# ControllerPrint.net
KiCad netlist of a schematic drawn in Altium Designer
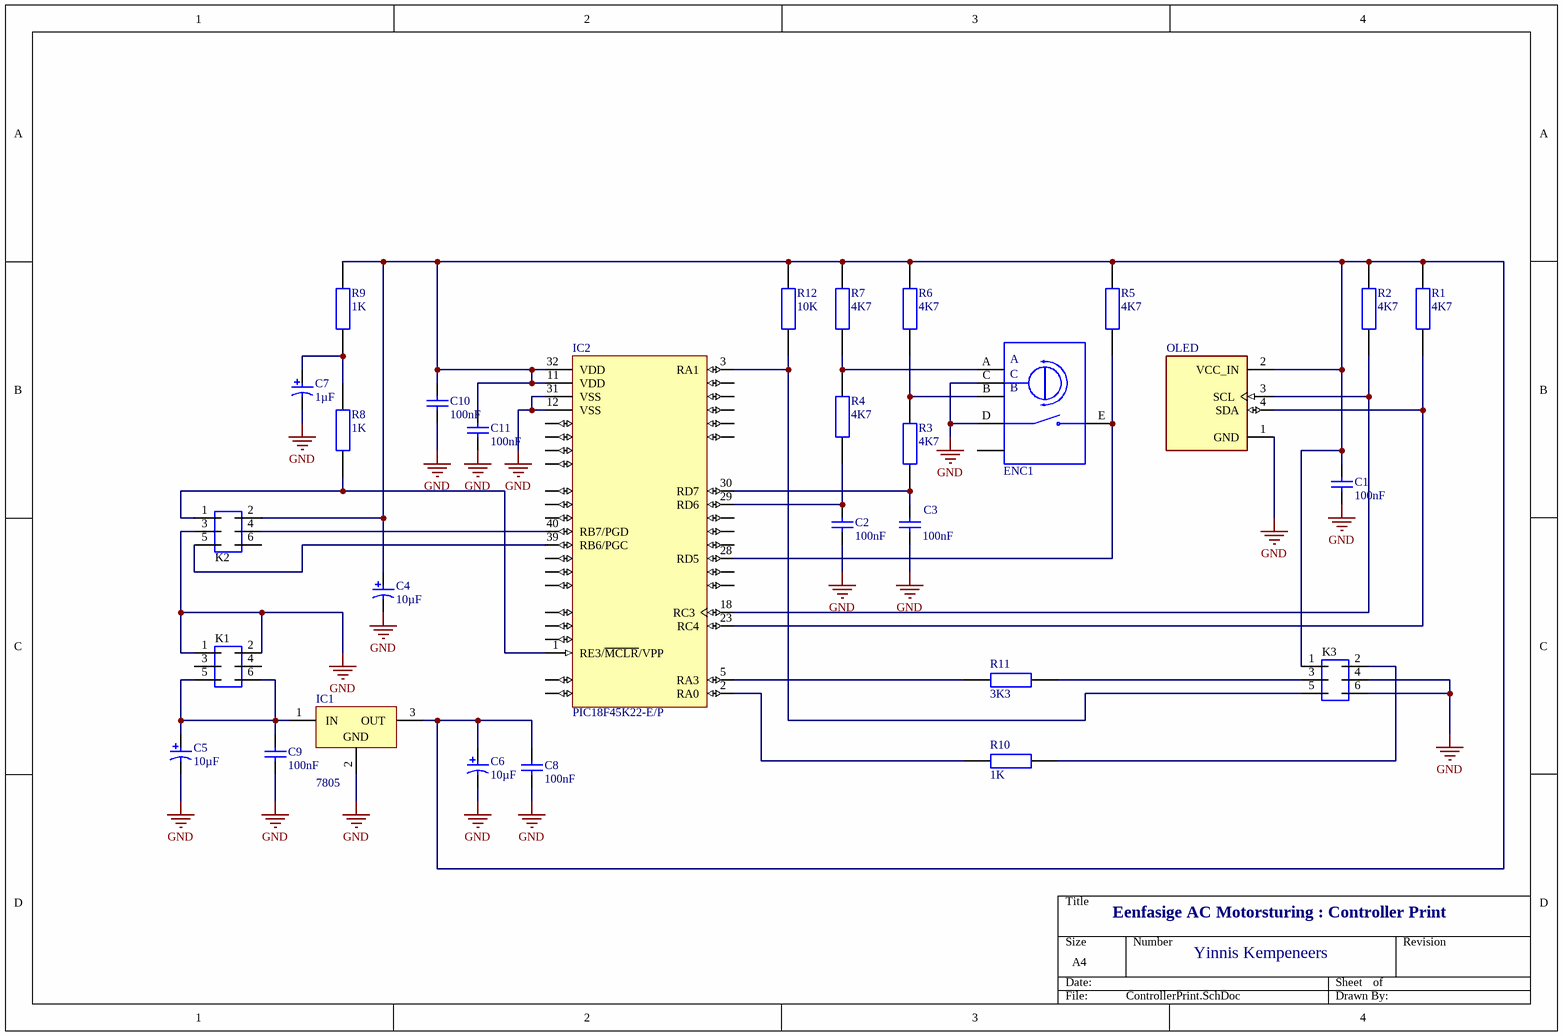
[diagram p0: ControllerPrint.SchDoc]

(export (version "E")
  (design (tool "Eeschema 10.0.6"))
  (components
    (comp (ref "C1")
      (value "100nF")
      (footprint "Capacitor 100nF")
      (libsource (lib "Schlib_Motorsturing") (part "Capacitor 100nF"))
    )
    (comp (ref "C2")
      (value "100nF")
      (footprint "Capacitor 100nF")
      (libsource (lib "Schlib_Motorsturing") (part "Capacitor 100nF"))
    )
    (comp (ref "C3")
      (value "100nF")
      (footprint "Capacitor 100nF")
      (libsource (lib "Schlib_Motorsturing") (part "Capacitor 100nF"))
    )
    (comp (ref "C4")
      (value "10µF")
      (footprint "Capacitor 10µF")
      (description "Aluminum Electrolytic Capacitor, 10 uF, +/- 20%, 50 V, -40 to 85 degC, 2-Pin THD, RoHS, Bulk")
      (fields (field (name "MANUFACTURER") "Panasonic") (field (name "TOLERANCE") "20%"))
      (libsource (lib "Schlib_Motorsturing") (part "Capacitor 10µF"))
    )
    (comp (ref "C5")
      (value "10µF")
      (footprint "Capacitor 10µF")
      (description "Aluminum Electrolytic Capacitor, 10 uF, +/- 20%, 50 V, -40 to 85 degC, 2-Pin THD, RoHS, Bulk")
      (fields (field (name "MANUFACTURER") "Panasonic") (field (name "TOLERANCE") "20%"))
      (libsource (lib "Schlib_Motorsturing") (part "Capacitor 10µF"))
    )
    (comp (ref "C6")
      (value "10µF")
      (footprint "Capacitor 10µF")
      (description "Aluminum Electrolytic Capacitor, 10 uF, +/- 20%, 50 V, -40 to 85 degC, 2-Pin THD, RoHS, Bulk")
      (fields (field (name "MANUFACTURER") "Panasonic") (field (name "TOLERANCE") "20%"))
      (libsource (lib "Schlib_Motorsturing") (part "Capacitor 10µF"))
    )
    (comp (ref "C7")
      (value "1µF")
      (footprint "Capacitor 10µF")
      (description "Aluminum 1µ Electrolytic Capacitor, 1 uF, +/- 20%, 50 V, -40 to 85 degC, 2-Pin THD, RoHS, Bulk")
      (fields (field (name "MANUFACTURER") "Panasonic") (field (name "TOLERANCE") "20%"))
      (libsource (lib "Schlib_Motorsturing") (part "Capacitor 10µF"))
    )
    (comp (ref "C8")
      (value "100nF")
      (footprint "Capacitor 100nF")
      (libsource (lib "Schlib_Motorsturing") (part "Capacitor 100nF"))
    )
    (comp (ref "C9")
      (value "100nF")
      (footprint "Capacitor 100nF")
      (libsource (lib "Schlib_Motorsturing") (part "Capacitor 100nF"))
    )
    (comp (ref "C10")
      (value "100nF")
      (footprint "Capacitor 100nF")
      (libsource (lib "Schlib_Motorsturing") (part "Capacitor 100nF"))
    )
    (comp (ref "C11")
      (value "100nF")
      (footprint "Capacitor 100nF")
      (libsource (lib "Schlib_Motorsturing") (part "Capacitor 100nF"))
    )
    (comp (ref "ENC1")
      (value "EC12E2424407")
      (footprint "ENC1_PCB")
      (description "Encoders 12mm 24 Res 24 Dtent 20mm op sectn w/ sw")
      (fields (field (name "MF") "ALPS"))
      (libsource (lib "Schlib1") (part "ENC1"))
    )
    (comp (ref "IC1")
      (value "7805")
      (footprint "MC7805CTG")
      (description "Positive Voltage Regulator, 1 A, 5 V, 0 to 125 degC, 3-Pin TO-220, RoHS, Tube")
      (fields (field (name "MANUFACTURER") "ON Semiconductor"))
      (libsource (lib "Schlib_Motorsturing") (part "MC7805CTG"))
    )
    (comp (ref "IC2")
      (value "PIC18F45K22-E/P")
      (footprint "PIC18F45K22-E/P")
      (fields (field (name "MANUFACTURER") "Microchip"))
      (libsource (lib "Schlib_Motorsturing") (part "PIC18F45K22-E/P"))
    )
    (comp (ref "K1")
      (value "~")
      (footprint "Pin3x2")
      (description "Male Header, Pitch 2.54 mm, 2 x 3 Position,  8.9 x 15.22 x 11.95 mm")
      (fields (field (name "MANUFACTURER") "Samtec"))
      (libsource (lib "Schlib_Motorsturing") (part "Connector3x2"))
    )
    (comp (ref "K2")
      (value "TSW-103-08-L-D")
      (footprint "Pin3x2")
      (description "Male Header, Pitch 2.54 mm, 2 x 3 Position,  8.9 x 15.22 x 11.95 mm")
      (fields (field (name "MANUFACTURER") "Samtec"))
      (libsource (lib "Schlib_Motorsturing") (part "Connector3x2"))
    )
    (comp (ref "K3")
      (value "TSW-103-08-L-D")
      (footprint "Pin3x2")
      (description "Male Header, Pitch 2.54 mm, 2 x 3 Position,  8.9 x 15.22 x 11.95 mm")
      (fields (field (name "MANUFACTURER") "Samtec"))
      (libsource (lib "Schlib_Motorsturing") (part "Connector3x2"))
    )
    (comp (ref "OLED")
      (value "OLED")
      (footprint "OLED")
      (description "0.96â€ 128 X 64 MONOCHROME GRAPHIC OLED DISPLAY MODULE - I2C")
      (fields (field (name "MF") "Display Module") (field (name "MP") "DM-OLED096-636"))
      (libsource (lib "Schlib_Motorsturing") (part "OLED"))
    )
    (comp (ref "R1")
      (value "4K7")
      (footprint "Resistor")
      (description "RES 4K7 OHM 0.6W 1% AXIAL")
      (fields (field (name "TOLERANCE") "1%"))
      (libsource (lib "Schlib_Motorsturing") (part "Resistor"))
    )
    (comp (ref "R2")
      (value "4K7")
      (footprint "Resistor")
      (description "RES 4K7 OHM 0.6W 1% AXIAL")
      (fields (field (name "TOLERANCE") "1%"))
      (libsource (lib "Schlib_Motorsturing") (part "Resistor"))
    )
    (comp (ref "R3")
      (value "4K7")
      (footprint "Resistor")
      (description "RES 4K7 OHM 0.6W 1% AXIAL")
      (fields (field (name "TOLERANCE") "1%"))
      (libsource (lib "Schlib1") (part "Resistor"))
    )
    (comp (ref "R4")
      (value "4K7")
      (footprint "Resistor")
      (description "RES 4K7 OHM 0.6W 1% AXIAL")
      (fields (field (name "TOLERANCE") "1%"))
      (libsource (lib "Schlib1") (part "Resistor"))
    )
    (comp (ref "R5")
      (value "4K7")
      (footprint "Resistor")
      (description "RES ?K OHM 0.6W 1% AXIAL")
      (fields (field (name "TOLERANCE") "1%"))
      (libsource (lib "Schlib_Motorsturing") (part "Resistor"))
    )
    (comp (ref "R6")
      (value "4K7")
      (footprint "Resistor")
      (description "RES 4K7 OHM 0.6W 1% AXIAL")
      (fields (field (name "TOLERANCE") "1%"))
      (libsource (lib "Schlib1") (part "Resistor"))
    )
    (comp (ref "R7")
      (value "4K7")
      (footprint "Resistor")
      (description "RES 4K7 OHM 0.6W 1% AXIAL")
      (fields (field (name "TOLERANCE") "1%"))
      (libsource (lib "Schlib1") (part "Resistor"))
    )
    (comp (ref "R8")
      (value "1K")
      (footprint "Resistor")
      (description "RES 1K OHM 0.6W 1% AXIAL")
      (fields (field (name "TOLERANCE") "1%"))
      (libsource (lib "Schlib_Motorsturing") (part "Resistor"))
    )
    (comp (ref "R9")
      (value "1K")
      (footprint "Resistor")
      (description "RES 1K OHM 0.6W 1% AXIAL")
      (fields (field (name "TOLERANCE") "1%"))
      (libsource (lib "Schlib_Motorsturing") (part "Resistor"))
    )
    (comp (ref "R10")
      (value "1K")
      (footprint "Resistor")
      (description "RES 1K OHM 0.6W 1% AXIAL")
      (fields (field (name "TOLERANCE") "1%"))
      (libsource (lib "Schlib_Motorsturing") (part "Resistor"))
    )
    (comp (ref "R11")
      (value "3K3")
      (footprint "Resistor")
      (description "RES 3K3 OHM 0.6W 1% AXIAL")
      (fields (field (name "TOLERANCE") "1%"))
      (libsource (lib "Schlib_Motorsturing") (part "Resistor"))
    )
    (comp (ref "R12")
      (value "10K")
      (footprint "Resistor")
      (description "RES 10K OHM 0.6W 1% AXIAL")
      (fields (field (name "TOLERANCE") "1%"))
      (libsource (lib "Schlib1") (part "Resistor"))
    )
  )
  (nets
    (net (code "1") (name "GND") (class "Default")
      (node (ref "C1") (pin "1") (pinfunction "1_1") (pintype "passive"))
      (node (ref "C10") (pin "1") (pinfunction "1_1") (pintype "passive"))
      (node (ref "C11") (pin "1") (pinfunction "1_1") (pintype "passive"))
      (node (ref "C2") (pin "1") (pinfunction "1_1") (pintype "passive"))
      (node (ref "C3") (pin "1") (pinfunction "1_1") (pintype "passive"))
      (node (ref "C4") (pin "2") (pinfunction "2_2") (pintype "passive"))
      (node (ref "C5") (pin "2") (pinfunction "2_2") (pintype "passive"))
      (node (ref "C6") (pin "2") (pinfunction "2_2") (pintype "passive"))
      (node (ref "C7") (pin "2") (pinfunction "2_2") (pintype "passive"))
      (node (ref "C8") (pin "1") (pinfunction "1_1") (pintype "passive"))
      (node (ref "C9") (pin "1") (pinfunction "1_1") (pintype "passive"))
      (node (ref "ENC1") (pin "C") (pinfunction "C_C") (pintype "passive"))
      (node (ref "ENC1") (pin "D") (pinfunction "COM_D") (pintype "passive"))
      (node (ref "IC1") (pin "2") (pinfunction "GND_2") (pintype "power_in"))
      (node (ref "IC2") (pin "12") (pinfunction "VSS_12") (pintype "power_in"))
      (node (ref "IC2") (pin "31") (pinfunction "VSS_31") (pintype "power_in"))
      (node (ref "K1") (pin "1") (pinfunction "1_1") (pintype "passive"))
      (node (ref "K1") (pin "2") (pinfunction "2_2") (pintype "passive"))
      (node (ref "K2") (pin "3") (pinfunction "3_3") (pintype "passive"))
      (node (ref "K3") (pin "4") (pinfunction "4_4") (pintype "passive"))
      (node (ref "K3") (pin "6") (pinfunction "6_6") (pintype "passive"))
      (node (ref "OLED") (pin "1") (pinfunction "GND_1") (pintype "power_in"))
    )
    (net (code "2") (name "Net-(C7-Pad1)") (class "Default")
      (node (ref "C7") (pin "1") (pinfunction "1_1") (pintype "passive"))
      (node (ref "R8") (pin "2") (pinfunction "2_2") (pintype "passive"))
      (node (ref "R9") (pin "1") (pinfunction "1_1") (pintype "passive"))
    )
    (net (code "3") (name "Net-(ENC1-NO)") (class "Default")
      (node (ref "ENC1") (pin "E") (pinfunction "NO_E") (pintype "passive"))
      (node (ref "IC2") (pin "28") (pinfunction "RD5_28") (pintype "bidirectional"))
      (node (ref "R5") (pin "1") (pinfunction "1_1") (pintype "passive"))
    )
    (net (code "4") (name "Net-(ENC1-PadA)") (class "Default")
      (node (ref "ENC1") (pin "A") (pinfunction "A_A") (pintype "passive"))
      (node (ref "R4") (pin "2") (pinfunction "2_2") (pintype "passive"))
      (node (ref "R7") (pin "1") (pinfunction "1_1") (pintype "passive"))
    )
    (net (code "5") (name "Net-(ENC1-PadB)") (class "Default")
      (node (ref "ENC1") (pin "B") (pinfunction "B_B") (pintype "passive"))
      (node (ref "R3") (pin "2") (pinfunction "2_2") (pintype "passive"))
      (node (ref "R6") (pin "1") (pinfunction "1_1") (pintype "passive"))
    )
    (net (code "6") (name "Net-(ENC1-SHIELD-PadS1)") (class "Default")
      (node (ref "ENC1") (pin "S1") (pinfunction "SHIELD_S1") (pintype "passive"))
      (node (ref "ENC1") (pin "S2") (pinfunction "SHIELD_S2") (pintype "passive"))
    )
    (net (code "7") (name "Net-(IC1-IN)") (class "Default")
      (node (ref "C5") (pin "1") (pinfunction "1_1") (pintype "passive"))
      (node (ref "C9") (pin "2") (pinfunction "2_2") (pintype "passive"))
      (node (ref "IC1") (pin "1") (pinfunction "IN_1") (pintype "power_in"))
      (node (ref "K1") (pin "5") (pinfunction "5_5") (pintype "passive"))
      (node (ref "K1") (pin "6") (pinfunction "6_6") (pintype "passive"))
    )
    (net (code "8") (name "Net-(IC1-OUT)") (class "Default")
      (node (ref "C1") (pin "2") (pinfunction "2_2") (pintype "passive"))
      (node (ref "C10") (pin "2") (pinfunction "2_2") (pintype "passive"))
      (node (ref "C11") (pin "2") (pinfunction "2_2") (pintype "passive"))
      (node (ref "C4") (pin "1") (pinfunction "1_1") (pintype "passive"))
      (node (ref "C6") (pin "1") (pinfunction "1_1") (pintype "passive"))
      (node (ref "C8") (pin "2") (pinfunction "2_2") (pintype "passive"))
      (node (ref "IC1") (pin "3") (pinfunction "OUT_3") (pintype "power_in"))
      (node (ref "IC2") (pin "11") (pinfunction "VDD_11") (pintype "power_in"))
      (node (ref "IC2") (pin "32") (pinfunction "VDD_32") (pintype "power_in"))
      (node (ref "K2") (pin "2") (pinfunction "2_2") (pintype "passive"))
      (node (ref "K3") (pin "1") (pinfunction "1_1") (pintype "passive"))
      (node (ref "OLED") (pin "2") (pinfunction "VCC_IN_2") (pintype "power_in"))
      (node (ref "R1") (pin "2") (pinfunction "2_2") (pintype "passive"))
      (node (ref "R12") (pin "2") (pinfunction "2_2") (pintype "passive"))
      (node (ref "R2") (pin "2") (pinfunction "2_2") (pintype "passive"))
      (node (ref "R5") (pin "2") (pinfunction "2_2") (pintype "passive"))
      (node (ref "R6") (pin "2") (pinfunction "2_2") (pintype "passive"))
      (node (ref "R7") (pin "2") (pinfunction "2_2") (pintype "passive"))
      (node (ref "R9") (pin "2") (pinfunction "2_2") (pintype "passive"))
    )
    (net (code "9") (name "Net-(IC2-RA0)") (class "Default")
      (node (ref "IC2") (pin "2") (pinfunction "RA0_2") (pintype "bidirectional"))
      (node (ref "R10") (pin "1") (pinfunction "1_1") (pintype "passive"))
    )
    (net (code "10") (name "Net-(IC2-RA1)") (class "Default")
      (node (ref "IC2") (pin "3") (pinfunction "RA1_3") (pintype "bidirectional"))
      (node (ref "K3") (pin "5") (pinfunction "5_5") (pintype "passive"))
      (node (ref "R12") (pin "1") (pinfunction "1_1") (pintype "passive"))
    )
    (net (code "11") (name "Net-(IC2-RA3)") (class "Default")
      (node (ref "IC2") (pin "5") (pinfunction "RA3_5") (pintype "bidirectional"))
      (node (ref "R11") (pin "1") (pinfunction "1_1") (pintype "passive"))
    )
    (net (code "12") (name "Net-(IC2-RB6{slash}PGC)") (class "Default")
      (node (ref "IC2") (pin "39") (pinfunction "RB6/PGC_39") (pintype "bidirectional"))
      (node (ref "K2") (pin "5") (pinfunction "5_5") (pintype "passive"))
    )
    (net (code "13") (name "Net-(IC2-RB7{slash}PGD)") (class "Default")
      (node (ref "IC2") (pin "40") (pinfunction "RB7/PGD_40") (pintype "bidirectional"))
      (node (ref "K2") (pin "4") (pinfunction "4_4") (pintype "passive"))
    )
    (net (code "14") (name "Net-(IC2-RC3)") (class "Default")
      (node (ref "IC2") (pin "18") (pinfunction "RC3_18") (pintype "bidirectional"))
      (node (ref "OLED") (pin "3") (pinfunction "SCL_3") (pintype "input"))
      (node (ref "R2") (pin "1") (pinfunction "1_1") (pintype "passive"))
    )
    (net (code "15") (name "Net-(IC2-RC4)") (class "Default")
      (node (ref "IC2") (pin "23") (pinfunction "RC4_23") (pintype "bidirectional"))
      (node (ref "OLED") (pin "4") (pinfunction "SDA_4") (pintype "bidirectional"))
      (node (ref "R1") (pin "1") (pinfunction "1_1") (pintype "passive"))
    )
    (net (code "16") (name "Net-(IC2-RD6)") (class "Default")
      (node (ref "C2") (pin "2") (pinfunction "2_2") (pintype "passive"))
      (node (ref "IC2") (pin "29") (pinfunction "RD6_29") (pintype "bidirectional"))
      (node (ref "R4") (pin "1") (pinfunction "1_1") (pintype "passive"))
    )
    (net (code "17") (name "Net-(IC2-RD7)") (class "Default")
      (node (ref "C3") (pin "2") (pinfunction "2_2") (pintype "passive"))
      (node (ref "IC2") (pin "30") (pinfunction "RD7_30") (pintype "bidirectional"))
      (node (ref "R3") (pin "1") (pinfunction "1_1") (pintype "passive"))
    )
    (net (code "18") (name "Net-(IC2-RE3{slash}~{MCLR}{slash}VPP)") (class "Default")
      (node (ref "IC2") (pin "1") (pinfunction "RE3/~{MCLR}/VPP_1") (pintype "input"))
      (node (ref "K2") (pin "1") (pinfunction "1_1") (pintype "passive"))
      (node (ref "R8") (pin "1") (pinfunction "1_1") (pintype "passive"))
    )
    (net (code "19") (name "Net-(K3-Pad2)") (class "Default")
      (node (ref "K3") (pin "2") (pinfunction "2_2") (pintype "passive"))
      (node (ref "R10") (pin "2") (pinfunction "2_2") (pintype "passive"))
    )
    (net (code "20") (name "Net-(K3-Pad3)") (class "Default")
      (node (ref "K3") (pin "3") (pinfunction "3_3") (pintype "passive"))
      (node (ref "R11") (pin "2") (pinfunction "2_2") (pintype "passive"))
    )
    (net (code "21") (name "unconnected-(IC2-RA2-Pad4)") (class "Default")
      (node (ref "IC2") (pin "4") (pinfunction "RA2_4") (pintype "bidirectional"))
    )
    (net (code "22") (name "unconnected-(IC2-RA4-Pad6)") (class "Default")
      (node (ref "IC2") (pin "6") (pinfunction "RA4_6") (pintype "bidirectional"))
    )
    (net (code "23") (name "unconnected-(IC2-RA5-Pad7)") (class "Default")
      (node (ref "IC2") (pin "7") (pinfunction "RA5_7") (pintype "bidirectional"))
    )
    (net (code "24") (name "unconnected-(IC2-RA6-Pad14)") (class "Default")
      (node (ref "IC2") (pin "14") (pinfunction "RA6_14") (pintype "bidirectional"))
    )
    (net (code "25") (name "unconnected-(IC2-RA7-Pad13)") (class "Default")
      (node (ref "IC2") (pin "13") (pinfunction "RA7_13") (pintype "bidirectional"))
    )
    (net (code "26") (name "unconnected-(IC2-RB0-Pad33)") (class "Default")
      (node (ref "IC2") (pin "33") (pinfunction "RB0_33") (pintype "bidirectional"))
    )
    (net (code "27") (name "unconnected-(IC2-RB1-Pad34)") (class "Default")
      (node (ref "IC2") (pin "34") (pinfunction "RB1_34") (pintype "bidirectional"))
    )
    (net (code "28") (name "unconnected-(IC2-RB2-Pad35)") (class "Default")
      (node (ref "IC2") (pin "35") (pinfunction "RB2_35") (pintype "bidirectional"))
    )
    (net (code "29") (name "unconnected-(IC2-RB3-Pad36)") (class "Default")
      (node (ref "IC2") (pin "36") (pinfunction "RB3_36") (pintype "bidirectional"))
    )
    (net (code "30") (name "unconnected-(IC2-RB4-Pad37)") (class "Default")
      (node (ref "IC2") (pin "37") (pinfunction "RB4_37") (pintype "bidirectional"))
    )
    (net (code "31") (name "unconnected-(IC2-RB5-Pad38)") (class "Default")
      (node (ref "IC2") (pin "38") (pinfunction "RB5_38") (pintype "bidirectional"))
    )
    (net (code "32") (name "unconnected-(IC2-RC0-Pad15)") (class "Default")
      (node (ref "IC2") (pin "15") (pinfunction "RC0_15") (pintype "bidirectional"))
    )
    (net (code "33") (name "unconnected-(IC2-RC1-Pad16)") (class "Default")
      (node (ref "IC2") (pin "16") (pinfunction "RC1_16") (pintype "bidirectional"))
    )
    (net (code "34") (name "unconnected-(IC2-RC2-Pad17)") (class "Default")
      (node (ref "IC2") (pin "17") (pinfunction "RC2_17") (pintype "bidirectional"))
    )
    (net (code "35") (name "unconnected-(IC2-RC5-Pad24)") (class "Default")
      (node (ref "IC2") (pin "24") (pinfunction "RC5_24") (pintype "bidirectional"))
    )
    (net (code "36") (name "unconnected-(IC2-RC6-Pad25)") (class "Default")
      (node (ref "IC2") (pin "25") (pinfunction "RC6_25") (pintype "bidirectional"))
    )
    (net (code "37") (name "unconnected-(IC2-RC7-Pad26)") (class "Default")
      (node (ref "IC2") (pin "26") (pinfunction "RC7_26") (pintype "bidirectional"))
    )
    (net (code "38") (name "unconnected-(IC2-RD0-Pad19)") (class "Default")
      (node (ref "IC2") (pin "19") (pinfunction "RD0_19") (pintype "bidirectional"))
    )
    (net (code "39") (name "unconnected-(IC2-RD1-Pad20)") (class "Default")
      (node (ref "IC2") (pin "20") (pinfunction "RD1_20") (pintype "bidirectional"))
    )
    (net (code "40") (name "unconnected-(IC2-RD2-Pad21)") (class "Default")
      (node (ref "IC2") (pin "21") (pinfunction "RD2_21") (pintype "bidirectional"))
    )
    (net (code "41") (name "unconnected-(IC2-RD3-Pad22)") (class "Default")
      (node (ref "IC2") (pin "22") (pinfunction "RD3_22") (pintype "bidirectional"))
    )
    (net (code "42") (name "unconnected-(IC2-RD4-Pad27)") (class "Default")
      (node (ref "IC2") (pin "27") (pinfunction "RD4_27") (pintype "bidirectional"))
    )
    (net (code "43") (name "unconnected-(IC2-RE0-Pad8)") (class "Default")
      (node (ref "IC2") (pin "8") (pinfunction "RE0_8") (pintype "bidirectional"))
    )
    (net (code "44") (name "unconnected-(IC2-RE1-Pad9)") (class "Default")
      (node (ref "IC2") (pin "9") (pinfunction "RE1_9") (pintype "bidirectional"))
    )
    (net (code "45") (name "unconnected-(IC2-RE2-Pad10)") (class "Default")
      (node (ref "IC2") (pin "10") (pinfunction "RE2_10") (pintype "bidirectional"))
    )
    (net (code "46") (name "unconnected-(K1-Pad3)") (class "Default")
      (node (ref "K1") (pin "3") (pinfunction "3_3") (pintype "passive"))
    )
    (net (code "47") (name "unconnected-(K1-Pad4)") (class "Default")
      (node (ref "K1") (pin "4") (pinfunction "4_4") (pintype "passive"))
    )
    (net (code "48") (name "unconnected-(K2-Pad6)") (class "Default")
      (node (ref "K2") (pin "6") (pinfunction "6_6") (pintype "passive"))
    )
  )
)
